# TRACTIAN_Low-Power-MCU.net
KiCad netlist of a schematic drawn in Altium Designer
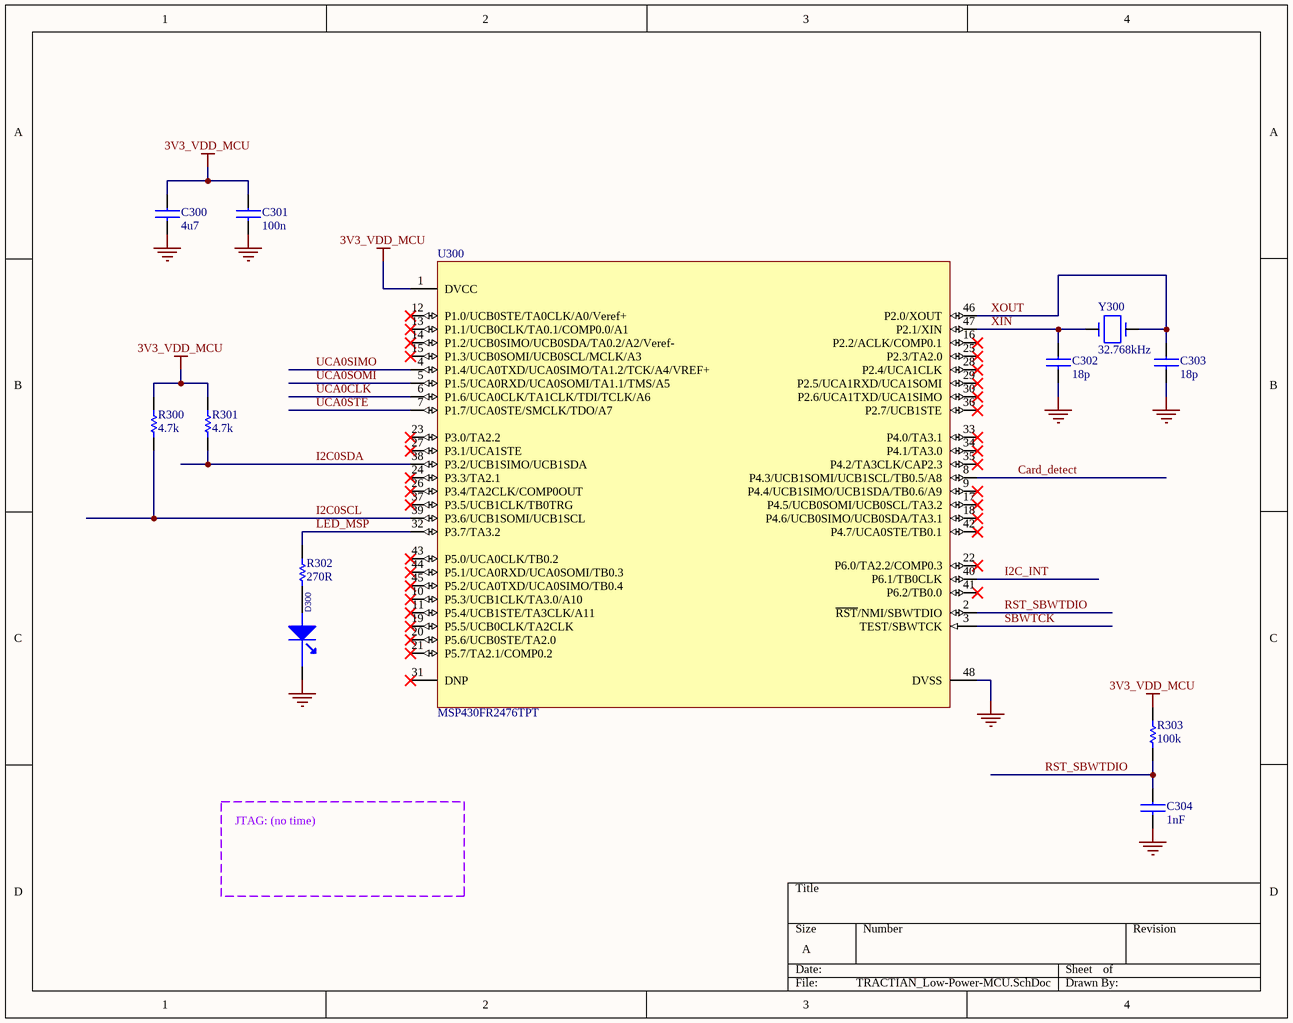
[diagram p0: TRACTIAN_Low-Power-MCU.SchDoc]

(export (version "E")
  (design (tool "Eeschema 10.0.6"))
  (components
    (comp (ref "C300")
      (value "4u7")
      (footprint "C0402")
      (description "CAP CER 4.7UF 10V 20% X5R 0402")
      (fields
        (field (name "MANUFACTURER") "TDK Corporation")
        (field (name "MANUFACTURER PART NUMBER") "C1005X5R1A475M")
        (field (name ".CHECKED PCB") "RF")
        (field (name ".CHECKED SCH") "RF")
      )
      (libsource (lib "TRACTIAN-HW-Challenge") (part "C1005X5R1A475M"))
    )
    (comp (ref "C301")
      (value "100n")
      (footprint "C0402")
      (description "CAP CER .10UF 50V X5R 10% 0402")
      (fields
        (field (name "MANUFACTURER") "TDK Corporation")
        (field (name "MANUFACTURER PART NUMBER") "C1005X5R1H104K")
      )
      (libsource (lib "TRACTIAN-HW-Challenge") (part "C1005X5R1H104K"))
    )
    (comp (ref "C302")
      (value "18p")
      (footprint "C0402")
      (description "CAP CER 18PF 50V C0G 5% 0402")
      (fields
        (field (name "MANUFACTURER") "TDK Corporation")
        (field (name "MANUFACTURER PART NUMBER") "C1005C0G1H180J")
      )
      (libsource (lib "Integrated_Library_RF_FEB_2012") (part "C1005C0G1H180J"))
    )
    (comp (ref "C303")
      (value "18p")
      (footprint "C0402")
      (description "CAP CER 18PF 50V C0G 5% 0402")
      (fields
        (field (name "MANUFACTURER") "TDK Corporation")
        (field (name "MANUFACTURER PART NUMBER") "C1005C0G1H180J")
      )
      (libsource (lib "Integrated_Library_RF_FEB_2012") (part "C1005C0G1H180J"))
    )
    (comp (ref "C304")
      (value "1nF")
      (footprint "C0402")
      (description "CAPACITOR")
      (libsource (lib "TRACTIAN-HW-Challenge") (part "Cap"))
    )
    (comp (ref "D300")
      (value "~")
      (footprint "LED_0603")
      (description "Generic LED 0603")
      (libsource (lib "TRACTIAN-HW-Challenge") (part "LED"))
    )
    (comp (ref "R300")
      (value "4.7k")
      (footprint "R0402")
      (description "Generic resistor")
      (libsource (lib "TRACTIAN-HW-Challenge") (part "Res"))
    )
    (comp (ref "R301")
      (value "4.7k")
      (footprint "R0402")
      (description "Generic resistor")
      (libsource (lib "TRACTIAN-HW-Challenge") (part "Res"))
    )
    (comp (ref "R302")
      (value "270R")
      (footprint "R0402")
      (description "Generic resistor")
      (libsource (lib "TRACTIAN-HW-Challenge") (part "Res"))
    )
    (comp (ref "R303")
      (value "100k")
      (footprint "R0402")
      (description "RES 100K OHM 1/16W 1% 0402 SMD")
      (fields
        (field (name "MANUFACTURER") "Stackpole Electronics Inc")
        (field (name "MANUFACTURER PART NUMBER") "RMCF0402FT100K")
      )
      (libsource (lib "TRACTIAN-HW-Challenge") (part "RMCF0402FT100K"))
    )
    (comp (ref "U300")
      (value "MSP430FR2476TPT")
      (footprint "LQFP-48")
      (description "MCU 16-BIT ULTRA-LOW-POWER MSP430FR2476TPT LQFP-48")
      (libsource (lib "TRACTIAN-HW-Challenge") (part "MSP430FR2476TPT"))
    )
    (comp (ref "Y300")
      (value "32.768kHz")
      (footprint "ABS06")
      (description "CRYSTAL 32.768 KHZ 9.0 PF SMD")
      (fields
        (field (name "MANUFACTURER") "Abracon Corporation")
        (field (name "MANUFACTURER PART NUMBER") "ABS06-32.768KHZ-9-1-T")
      )
      (libsource (lib "TRACTIAN-HW-Challenge") (part "ABS06-32.768KHZ-9-1-T"))
    )
  )
  (nets
    (net (code "1") (name "/Card_detect") (class "Default")
      (node (ref "U300") (pin "8") (pinfunction "P4.3/UCB1SOMI/UCB1SCL/TB0.5/A8_8") (pintype "bidirectional"))
    )
    (net (code "2") (name "/I2C0SCL") (class "Default")
      (node (ref "R300") (pin "1") (pinfunction "1_1") (pintype "passive"))
      (node (ref "U300") (pin "39") (pinfunction "P3.6/UCB1SOMI/UCB1SCL_39") (pintype "bidirectional"))
    )
    (net (code "3") (name "/I2C0SDA") (class "Default")
      (node (ref "R301") (pin "1") (pinfunction "1_1") (pintype "passive"))
      (node (ref "U300") (pin "38") (pinfunction "P3.2/UCB1SIMO/UCB1SDA_38") (pintype "bidirectional"))
    )
    (net (code "4") (name "/I2C_INT") (class "Default")
      (node (ref "U300") (pin "40") (pinfunction "P6.1/TB0CLK_40") (pintype "bidirectional"))
    )
    (net (code "5") (name "/LED_MSP") (class "Default")
      (node (ref "R302") (pin "2") (pinfunction "2_2") (pintype "passive"))
      (node (ref "U300") (pin "32") (pinfunction "P3.7/TA3.2_32") (pintype "bidirectional"))
    )
    (net (code "6") (name "/RST_SBWTDIO") (class "Default")
      (node (ref "C304") (pin "1") (pinfunction "1_1") (pintype "passive"))
      (node (ref "R303") (pin "1") (pinfunction "1_1") (pintype "passive"))
      (node (ref "U300") (pin "2") (pinfunction "~{RST}/NMI/SBWTDIO_2") (pintype "bidirectional"))
    )
    (net (code "7") (name "/SBWTCK") (class "Default")
      (node (ref "U300") (pin "3") (pinfunction "TEST/SBWTCK_3") (pintype "input"))
    )
    (net (code "8") (name "/UCA0CLK") (class "Default")
      (node (ref "U300") (pin "6") (pinfunction "P1.6/UCA0CLK/TA1CLK/TDI/TCLK/A6_6") (pintype "bidirectional"))
    )
    (net (code "9") (name "/UCA0SIMO") (class "Default")
      (node (ref "U300") (pin "4") (pinfunction "P1.4/UCA0TXD/UCA0SIMO/TA1.2/TCK/A4/VREF+_4") (pintype "bidirectional"))
    )
    (net (code "10") (name "/UCA0SOMI") (class "Default")
      (node (ref "U300") (pin "5") (pinfunction "P1.5/UCA0RXD/UCA0SOMI/TA1.1/TMS/A5_5") (pintype "bidirectional"))
    )
    (net (code "11") (name "/UCA0STE") (class "Default")
      (node (ref "U300") (pin "7") (pinfunction "P1.7/UCA0STE/SMCLK/TDO/A7_7") (pintype "bidirectional"))
    )
    (net (code "12") (name "/XIN") (class "Default")
      (node (ref "C302") (pin "1") (pinfunction "1_1") (pintype "passive"))
      (node (ref "U300") (pin "47") (pinfunction "P2.1/XIN_47") (pintype "bidirectional"))
      (node (ref "Y300") (pin "1") (pinfunction "1_1") (pintype "passive"))
    )
    (net (code "13") (name "/XOUT") (class "Default")
      (node (ref "C303") (pin "1") (pinfunction "1_1") (pintype "passive"))
      (node (ref "U300") (pin "46") (pinfunction "P2.0/XOUT_46") (pintype "bidirectional"))
      (node (ref "Y300") (pin "2") (pinfunction "2_2") (pintype "passive"))
    )
    (net (code "14") (name "3V3_VDD_MCU") (class "Default")
      (node (ref "C300") (pin "1") (pinfunction "1_1") (pintype "passive"))
      (node (ref "C301") (pin "1") (pinfunction "1_1") (pintype "passive"))
      (node (ref "R300") (pin "2") (pinfunction "2_2") (pintype "passive"))
      (node (ref "R301") (pin "2") (pinfunction "2_2") (pintype "passive"))
      (node (ref "R303") (pin "2") (pinfunction "2_2") (pintype "passive"))
      (node (ref "U300") (pin "1") (pinfunction "DVCC_1") (pintype "power_in"))
    )
    (net (code "15") (name "GND") (class "Default")
      (node (ref "C300") (pin "2") (pinfunction "2_2") (pintype "passive"))
      (node (ref "C301") (pin "2") (pinfunction "2_2") (pintype "passive"))
      (node (ref "C302") (pin "2") (pinfunction "2_2") (pintype "passive"))
      (node (ref "C303") (pin "2") (pinfunction "2_2") (pintype "passive"))
      (node (ref "C304") (pin "2") (pinfunction "2_2") (pintype "passive"))
      (node (ref "D300") (pin "1") (pinfunction "cathode_1") (pintype "passive"))
      (node (ref "U300") (pin "48") (pinfunction "DVSS_48") (pintype "power_in"))
    )
    (net (code "16") (name "Net-(D300-ANODE)") (class "Default")
      (node (ref "D300") (pin "2") (pinfunction "ANODE_2") (pintype "passive"))
      (node (ref "R302") (pin "1") (pinfunction "1_1") (pintype "passive"))
    )
    (net (code "17") (name "unconnected-(U300-DNP-Pad31)") (class "Default")
      (node (ref "U300") (pin "31") (pinfunction "DNP_31") (pintype "passive+no_connect"))
    )
    (net (code "18") (name "unconnected-(U300-P1.0{slash}UCB0STE{slash}TA0CLK{slash}A0{slash}Veref+-Pad12)") (class "Default")
      (node (ref "U300") (pin "12") (pinfunction "P1.0/UCB0STE/TA0CLK/A0/Veref+_12") (pintype "bidirectional+no_connect"))
    )
    (net (code "19") (name "unconnected-(U300-P1.1{slash}UCB0CLK{slash}TA0.1{slash}COMP0.0{slash}A1-Pad13)") (class "Default")
      (node (ref "U300") (pin "13") (pinfunction "P1.1/UCB0CLK/TA0.1/COMP0.0/A1_13") (pintype "bidirectional+no_connect"))
    )
    (net (code "20") (name "unconnected-(U300-P1.2{slash}UCB0SIMO{slash}UCB0SDA{slash}TA0.2{slash}A2{slash}Veref--Pad14)") (class "Default")
      (node (ref "U300") (pin "14") (pinfunction "P1.2/UCB0SIMO/UCB0SDA/TA0.2/A2/Veref-_14") (pintype "bidirectional+no_connect"))
    )
    (net (code "21") (name "unconnected-(U300-P1.3{slash}UCB0SOMI{slash}UCB0SCL{slash}MCLK{slash}A3-Pad15)") (class "Default")
      (node (ref "U300") (pin "15") (pinfunction "P1.3/UCB0SOMI/UCB0SCL/MCLK/A3_15") (pintype "bidirectional+no_connect"))
    )
    (net (code "22") (name "unconnected-(U300-P2.2{slash}ACLK{slash}COMP0.1-Pad16)") (class "Default")
      (node (ref "U300") (pin "16") (pinfunction "P2.2/ACLK/COMP0.1_16") (pintype "bidirectional+no_connect"))
    )
    (net (code "23") (name "unconnected-(U300-P2.3{slash}TA2.0-Pad25)") (class "Default")
      (node (ref "U300") (pin "25") (pinfunction "P2.3/TA2.0_25") (pintype "bidirectional+no_connect"))
    )
    (net (code "24") (name "unconnected-(U300-P2.4{slash}UCA1CLK-Pad28)") (class "Default")
      (node (ref "U300") (pin "28") (pinfunction "P2.4/UCA1CLK_28") (pintype "bidirectional+no_connect"))
    )
    (net (code "25") (name "unconnected-(U300-P2.5{slash}UCA1RXD{slash}UCA1SOMI-Pad29)") (class "Default")
      (node (ref "U300") (pin "29") (pinfunction "P2.5/UCA1RXD/UCA1SOMI_29") (pintype "bidirectional+no_connect"))
    )
    (net (code "26") (name "unconnected-(U300-P2.6{slash}UCA1TXD{slash}UCA1SIMO-Pad30)") (class "Default")
      (node (ref "U300") (pin "30") (pinfunction "P2.6/UCA1TXD/UCA1SIMO_30") (pintype "bidirectional+no_connect"))
    )
    (net (code "27") (name "unconnected-(U300-P2.7{slash}UCB1STE-Pad36)") (class "Default")
      (node (ref "U300") (pin "36") (pinfunction "P2.7/UCB1STE_36") (pintype "bidirectional+no_connect"))
    )
    (net (code "28") (name "unconnected-(U300-P3.0{slash}TA2.2-Pad23)") (class "Default")
      (node (ref "U300") (pin "23") (pinfunction "P3.0/TA2.2_23") (pintype "bidirectional+no_connect"))
    )
    (net (code "29") (name "unconnected-(U300-P3.1{slash}UCA1STE-Pad27)") (class "Default")
      (node (ref "U300") (pin "27") (pinfunction "P3.1/UCA1STE_27") (pintype "bidirectional+no_connect"))
    )
    (net (code "30") (name "unconnected-(U300-P3.3{slash}TA2.1-Pad24)") (class "Default")
      (node (ref "U300") (pin "24") (pinfunction "P3.3/TA2.1_24") (pintype "bidirectional+no_connect"))
    )
    (net (code "31") (name "unconnected-(U300-P3.4{slash}TA2CLK{slash}COMP0OUT-Pad26)") (class "Default")
      (node (ref "U300") (pin "26") (pinfunction "P3.4/TA2CLK/COMP0OUT_26") (pintype "bidirectional+no_connect"))
    )
    (net (code "32") (name "unconnected-(U300-P3.5{slash}UCB1CLK{slash}TB0TRG-Pad37)") (class "Default")
      (node (ref "U300") (pin "37") (pinfunction "P3.5/UCB1CLK/TB0TRG_37") (pintype "bidirectional+no_connect"))
    )
    (net (code "33") (name "unconnected-(U300-P4.0{slash}TA3.1-Pad33)") (class "Default")
      (node (ref "U300") (pin "33") (pinfunction "P4.0/TA3.1_33") (pintype "bidirectional+no_connect"))
    )
    (net (code "34") (name "unconnected-(U300-P4.1{slash}TA3.0-Pad34)") (class "Default")
      (node (ref "U300") (pin "34") (pinfunction "P4.1/TA3.0_34") (pintype "bidirectional+no_connect"))
    )
    (net (code "35") (name "unconnected-(U300-P4.2{slash}TA3CLK{slash}CAP2.3-Pad35)") (class "Default")
      (node (ref "U300") (pin "35") (pinfunction "P4.2/TA3CLK/CAP2.3_35") (pintype "bidirectional+no_connect"))
    )
    (net (code "36") (name "unconnected-(U300-P4.4{slash}UCB1SIMO{slash}UCB1SDA{slash}TB0.6{slash}A9-Pad9)") (class "Default")
      (node (ref "U300") (pin "9") (pinfunction "P4.4/UCB1SIMO/UCB1SDA/TB0.6/A9_9") (pintype "bidirectional+no_connect"))
    )
    (net (code "37") (name "unconnected-(U300-P4.5{slash}UCB0SOMI{slash}UCB0SCL{slash}TA3.2-Pad17)") (class "Default")
      (node (ref "U300") (pin "17") (pinfunction "P4.5/UCB0SOMI/UCB0SCL/TA3.2_17") (pintype "bidirectional+no_connect"))
    )
    (net (code "38") (name "unconnected-(U300-P4.6{slash}UCB0SIMO{slash}UCB0SDA{slash}TA3.1-Pad18)") (class "Default")
      (node (ref "U300") (pin "18") (pinfunction "P4.6/UCB0SIMO/UCB0SDA/TA3.1_18") (pintype "bidirectional+no_connect"))
    )
    (net (code "39") (name "unconnected-(U300-P4.7{slash}UCA0STE{slash}TB0.1-Pad42)") (class "Default")
      (node (ref "U300") (pin "42") (pinfunction "P4.7/UCA0STE/TB0.1_42") (pintype "bidirectional+no_connect"))
    )
    (net (code "40") (name "unconnected-(U300-P5.0{slash}UCA0CLK{slash}TB0.2-Pad43)") (class "Default")
      (node (ref "U300") (pin "43") (pinfunction "P5.0/UCA0CLK/TB0.2_43") (pintype "bidirectional+no_connect"))
    )
    (net (code "41") (name "unconnected-(U300-P5.1{slash}UCA0RXD{slash}UCA0SOMI{slash}TB0.3-Pad44)") (class "Default")
      (node (ref "U300") (pin "44") (pinfunction "P5.1/UCA0RXD/UCA0SOMI/TB0.3_44") (pintype "bidirectional+no_connect"))
    )
    (net (code "42") (name "unconnected-(U300-P5.2{slash}UCA0TXD{slash}UCA0SIMO{slash}TB0.4-Pad45)") (class "Default")
      (node (ref "U300") (pin "45") (pinfunction "P5.2/UCA0TXD/UCA0SIMO/TB0.4_45") (pintype "bidirectional+no_connect"))
    )
    (net (code "43") (name "unconnected-(U300-P5.3{slash}UCB1CLK{slash}TA3.0{slash}A10-Pad10)") (class "Default")
      (node (ref "U300") (pin "10") (pinfunction "P5.3/UCB1CLK/TA3.0/A10_10") (pintype "bidirectional+no_connect"))
    )
    (net (code "44") (name "unconnected-(U300-P5.4{slash}UCB1STE{slash}TA3CLK{slash}A11-Pad11)") (class "Default")
      (node (ref "U300") (pin "11") (pinfunction "P5.4/UCB1STE/TA3CLK/A11_11") (pintype "bidirectional+no_connect"))
    )
    (net (code "45") (name "unconnected-(U300-P5.5{slash}UCB0CLK{slash}TA2CLK-Pad19)") (class "Default")
      (node (ref "U300") (pin "19") (pinfunction "P5.5/UCB0CLK/TA2CLK_19") (pintype "bidirectional+no_connect"))
    )
    (net (code "46") (name "unconnected-(U300-P5.6{slash}UCB0STE{slash}TA2.0-Pad20)") (class "Default")
      (node (ref "U300") (pin "20") (pinfunction "P5.6/UCB0STE/TA2.0_20") (pintype "bidirectional+no_connect"))
    )
    (net (code "47") (name "unconnected-(U300-P5.7{slash}TA2.1{slash}COMP0.2-Pad21)") (class "Default")
      (node (ref "U300") (pin "21") (pinfunction "P5.7/TA2.1/COMP0.2_21") (pintype "bidirectional+no_connect"))
    )
    (net (code "48") (name "unconnected-(U300-P6.0{slash}TA2.2{slash}COMP0.3-Pad22)") (class "Default")
      (node (ref "U300") (pin "22") (pinfunction "P6.0/TA2.2/COMP0.3_22") (pintype "bidirectional+no_connect"))
    )
    (net (code "49") (name "unconnected-(U300-P6.2{slash}TB0.0-Pad41)") (class "Default")
      (node (ref "U300") (pin "41") (pinfunction "P6.2/TB0.0_41") (pintype "bidirectional+no_connect"))
    )
  )
)
